# pulsegen.net
KiCad netlist of a schematic drawn in EAGLE
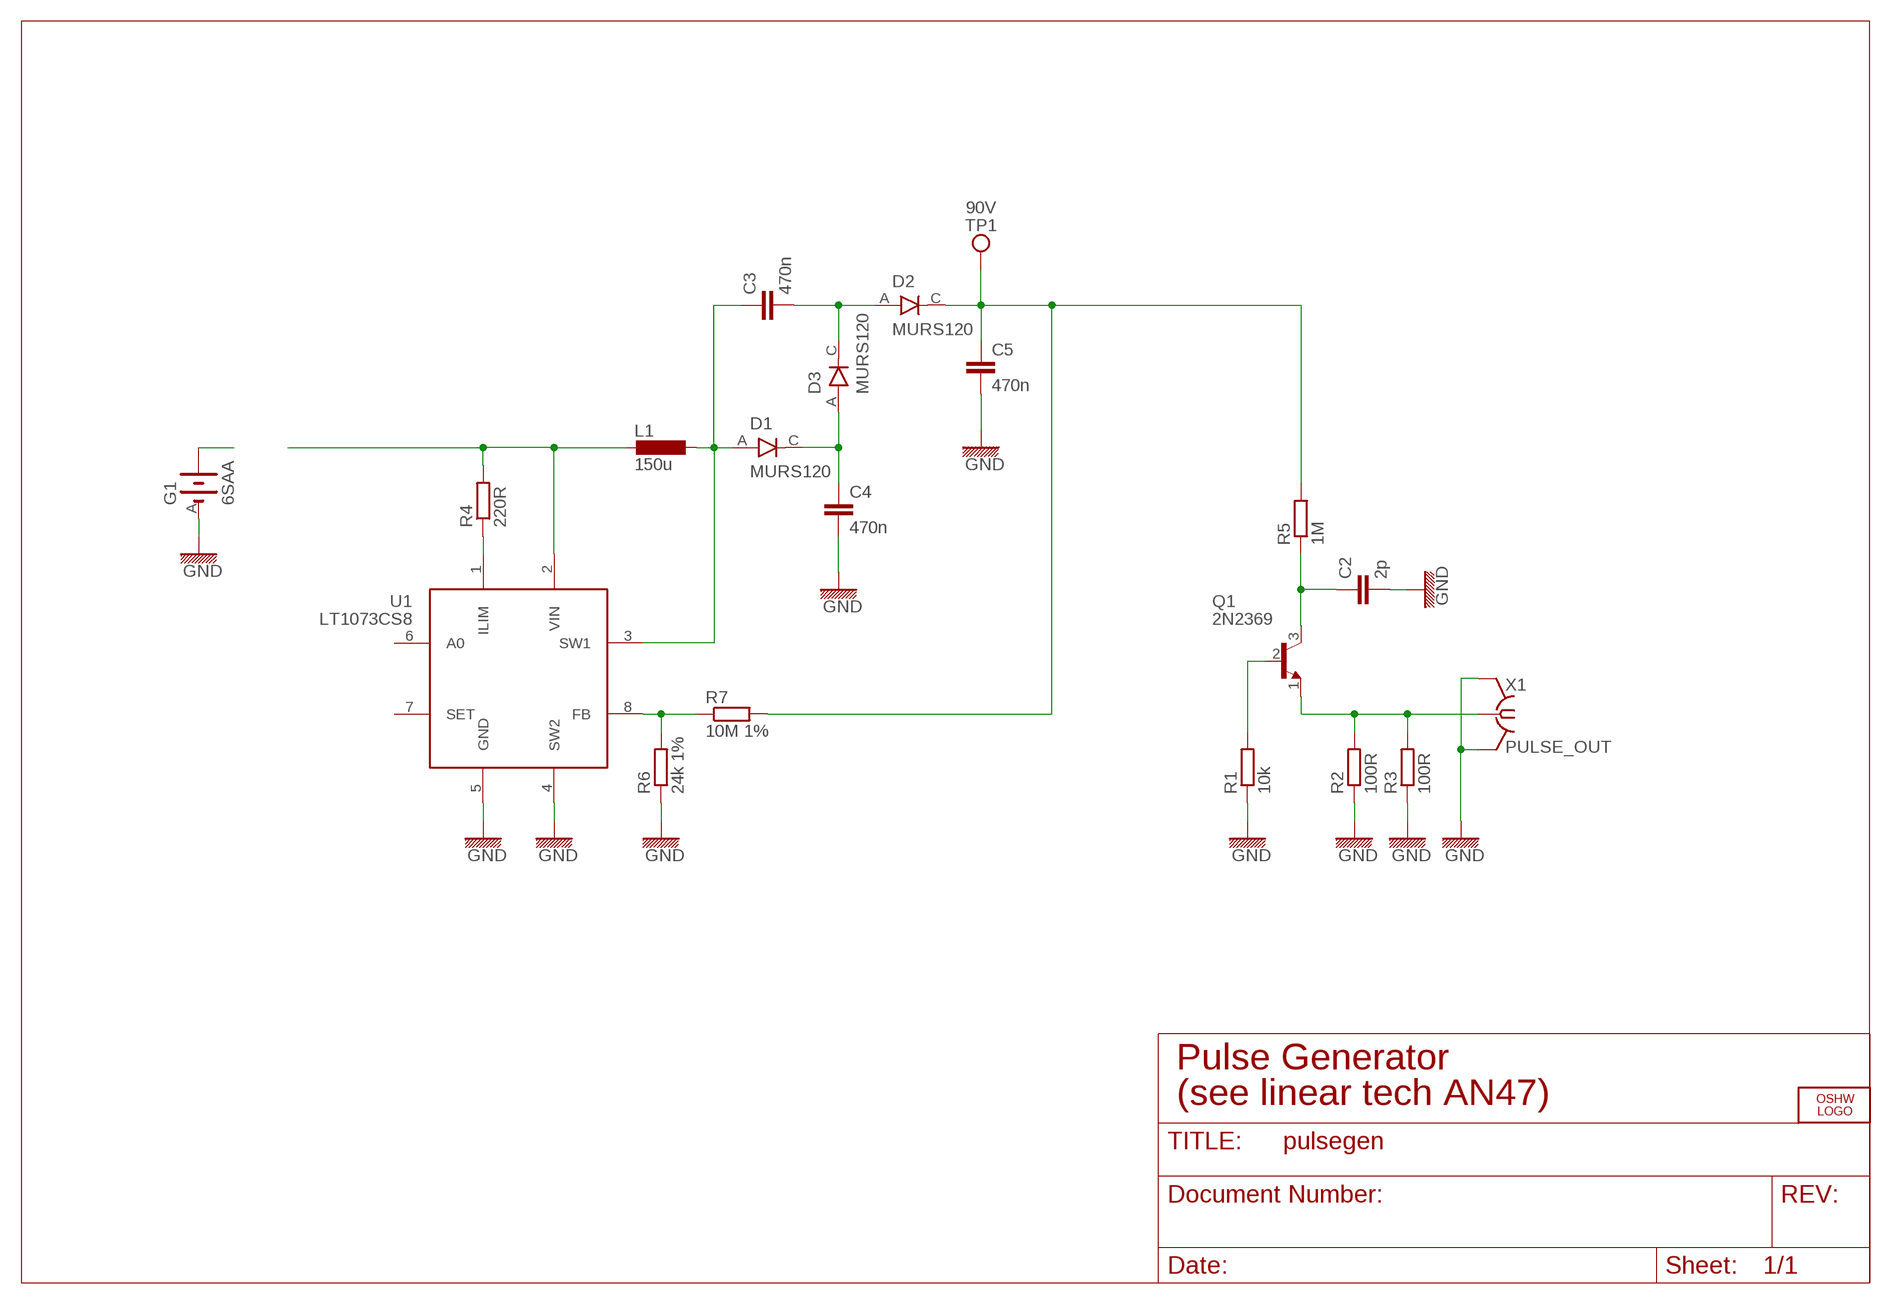
[diagram p0: schematic, sheet 1]

(export (version "E")
  (design (tool "Eeschema 10.0.6"))
  (components
    (comp (ref "C2")
      (value "2p")
      (footprint "eagle-import:0805")
      (libsource (lib "eagle-import") (part "C-EU_0805"))
    )
    (comp (ref "C3")
      (value "470n")
      (footprint "eagle-import:1210")
      (libsource (lib "eagle-import") (part "C-EU_1210"))
    )
    (comp (ref "C4")
      (value "470n")
      (footprint "eagle-import:1210")
      (libsource (lib "eagle-import") (part "C-EU_1210"))
    )
    (comp (ref "C5")
      (value "470n")
      (footprint "eagle-import:1210")
      (libsource (lib "eagle-import") (part "C-EU_1210"))
    )
    (comp (ref "D1")
      (value "MURS120")
      (footprint "eagle-import:SMB_DIODE")
      (libsource (lib "eagle-import") (part "D-EU"))
    )
    (comp (ref "D2")
      (value "MURS120")
      (footprint "eagle-import:SMB_DIODE")
      (libsource (lib "eagle-import") (part "D-EU"))
    )
    (comp (ref "D3")
      (value "MURS120")
      (footprint "eagle-import:SMB_DIODE")
      (libsource (lib "eagle-import") (part "D-EU"))
    )
    (comp (ref "G1")
      (value "6SAA")
      (footprint "eagle-import:6SAA")
      (libsource (lib "eagle-import") (part "BATTERY_6SAA"))
    )
    (comp (ref "L1")
      (value "150u")
      (footprint "eagle-import:L_WE_PD_M")
      (libsource (lib "eagle-import") (part "L-EU_WE_PD_M"))
    )
    (comp (ref "LOGO1")
      (value "OSHW_LOGO_FILLX0100-NT")
      (footprint "eagle-import:OSHW_FILLX100_NOTEXT")
      (libsource (lib "eagle-import") (part "OSHW_LOGO_FILLX0100-NT"))
    )
    (comp (ref "Q1")
      (value "2N2369")
      (footprint "eagle-import:TO18")
      (libsource (lib "eagle-import") (part "TRANS_NPN_TO18_EBC"))
    )
    (comp (ref "R1")
      (value "10k")
      (footprint "eagle-import:0805")
      (libsource (lib "eagle-import") (part "R-EU_0805"))
    )
    (comp (ref "R2")
      (value "100R")
      (footprint "eagle-import:0805")
      (libsource (lib "eagle-import") (part "R-EU_0805"))
    )
    (comp (ref "R3")
      (value "100R")
      (footprint "eagle-import:0805")
      (libsource (lib "eagle-import") (part "R-EU_0805"))
    )
    (comp (ref "R4")
      (value "220R")
      (footprint "eagle-import:0805")
      (libsource (lib "eagle-import") (part "R-EU_0805"))
    )
    (comp (ref "R5")
      (value "1M")
      (footprint "eagle-import:0805")
      (libsource (lib "eagle-import") (part "R-EU_0805"))
    )
    (comp (ref "R6")
      (value "24k 1%")
      (footprint "eagle-import:0805")
      (libsource (lib "eagle-import") (part "R-EU_0805"))
    )
    (comp (ref "R7")
      (value "10M 1%")
      (footprint "eagle-import:0805")
      (libsource (lib "eagle-import") (part "R-EU_0805"))
    )
    (comp (ref "TP1")
      (value "90V")
      (footprint "eagle-import:TP_1X1")
      (libsource (lib "eagle-import") (part "TESTPAD"))
    )
    (comp (ref "U1")
      (value "LT1073CS8")
      (footprint "eagle-import:SO8")
      (libsource (lib "eagle-import") (part "LT1073CS8"))
    )
    (comp (ref "X1")
      (value "PULSE_OUT")
      (footprint "eagle-import:BNC-EDGE-BIVB")
      (libsource (lib "eagle-import") (part "BNC-F"))
    )
  )
  (nets
    (net (code "1") (name "GND") (class "Default")
      (node (ref "C2") (pin "2") (pinfunction "2_2") (pintype "passive"))
      (node (ref "C4") (pin "2") (pinfunction "2_2") (pintype "passive"))
      (node (ref "C5") (pin "2") (pinfunction "2_2") (pintype "passive"))
      (node (ref "G1") (pin "A") (pinfunction "A_A") (pintype "passive"))
      (node (ref "R1") (pin "1") (pinfunction "1_1") (pintype "passive"))
      (node (ref "R2") (pin "1") (pinfunction "1_1") (pintype "passive"))
      (node (ref "R3") (pin "1") (pinfunction "1_1") (pintype "passive"))
      (node (ref "R6") (pin "1") (pinfunction "1_1") (pintype "passive"))
      (node (ref "U1") (pin "4") (pinfunction "SW2_4") (pintype "bidirectional"))
      (node (ref "U1") (pin "5") (pinfunction "GND_5") (pintype "bidirectional"))
      (node (ref "X1") (pin "GND@1") (pinfunction "GND_GND@1") (pintype "power_in"))
      (node (ref "X1") (pin "GND@2") (pinfunction "GND_GND@2") (pintype "power_in"))
    )
    (net (code "2") (name "Net-(C3-Pad2)") (class "Default")
      (node (ref "C3") (pin "2") (pinfunction "2_2") (pintype "passive"))
      (node (ref "D2") (pin "A") (pinfunction "A_A") (pintype "passive"))
      (node (ref "D3") (pin "C") (pinfunction "C_C") (pintype "passive"))
    )
    (net (code "3") (name "Net-(C4-Pad1)") (class "Default")
      (node (ref "C4") (pin "1") (pinfunction "1_1") (pintype "passive"))
      (node (ref "D1") (pin "C") (pinfunction "C_C") (pintype "passive"))
      (node (ref "D3") (pin "A") (pinfunction "A_A") (pintype "passive"))
    )
    (net (code "4") (name "Net-(C5-Pad1)") (class "Default")
      (node (ref "C5") (pin "1") (pinfunction "1_1") (pintype "passive"))
      (node (ref "D2") (pin "C") (pinfunction "C_C") (pintype "passive"))
      (node (ref "R5") (pin "2") (pinfunction "2_2") (pintype "passive"))
      (node (ref "R7") (pin "2") (pinfunction "2_2") (pintype "passive"))
      (node (ref "TP1") (pin "TP") (pinfunction "TP_TP") (pintype "bidirectional"))
    )
    (net (code "5") (name "Net-(Q1-B)") (class "Default")
      (node (ref "Q1") (pin "2") (pinfunction "B_2") (pintype "passive"))
      (node (ref "R1") (pin "2") (pinfunction "2_2") (pintype "passive"))
    )
    (net (code "6") (name "Net-(Q1-C)") (class "Default")
      (node (ref "C2") (pin "1") (pinfunction "1_1") (pintype "passive"))
      (node (ref "Q1") (pin "3") (pinfunction "C_3") (pintype "passive"))
      (node (ref "R5") (pin "1") (pinfunction "1_1") (pintype "passive"))
    )
    (net (code "7") (name "Net-(Q1-E)") (class "Default")
      (node (ref "Q1") (pin "1") (pinfunction "E_1") (pintype "passive"))
      (node (ref "R2") (pin "2") (pinfunction "2_2") (pintype "passive"))
      (node (ref "R3") (pin "2") (pinfunction "2_2") (pintype "passive"))
      (node (ref "X1") (pin "C") (pinfunction "1_C") (pintype "passive"))
    )
    (net (code "8") (name "Net-(U1-FB)") (class "Default")
      (node (ref "R6") (pin "2") (pinfunction "2_2") (pintype "passive"))
      (node (ref "R7") (pin "1") (pinfunction "1_1") (pintype "passive"))
      (node (ref "U1") (pin "8") (pinfunction "FB_8") (pintype "bidirectional"))
    )
    (net (code "9") (name "Net-(U1-ILIM)") (class "Default")
      (node (ref "R4") (pin "1") (pinfunction "1_1") (pintype "passive"))
      (node (ref "U1") (pin "1") (pinfunction "ILIM_1") (pintype "bidirectional"))
    )
    (net (code "10") (name "Net-(U1-SW1)") (class "Default")
      (node (ref "C3") (pin "1") (pinfunction "1_1") (pintype "passive"))
      (node (ref "D1") (pin "A") (pinfunction "A_A") (pintype "passive"))
      (node (ref "L1") (pin "1") (pinfunction "1_1") (pintype "passive"))
      (node (ref "U1") (pin "3") (pinfunction "SW1_3") (pintype "bidirectional"))
    )
    (net (code "11") (name "Net-(U1-VIN)") (class "Default")
      (node (ref "L1") (pin "2") (pinfunction "2_2") (pintype "passive"))
      (node (ref "R4") (pin "2") (pinfunction "2_2") (pintype "passive"))
      (node (ref "U1") (pin "2") (pinfunction "VIN_2") (pintype "bidirectional"))
    )
    (net (code "12") (name "unconnected-(G1-PadC)") (class "Default")
      (node (ref "G1") (pin "C") (pinfunction "C_C") (pintype "passive"))
    )
    (net (code "13") (name "unconnected-(U1-A0-Pad6)") (class "Default")
      (node (ref "U1") (pin "6") (pinfunction "A0_6") (pintype "bidirectional"))
    )
    (net (code "14") (name "unconnected-(U1-SET-Pad7)") (class "Default")
      (node (ref "U1") (pin "7") (pinfunction "SET_7") (pintype "bidirectional"))
    )
  )
)
